# POWER_IN.net
KiCad netlist of a schematic drawn in Altium Designer
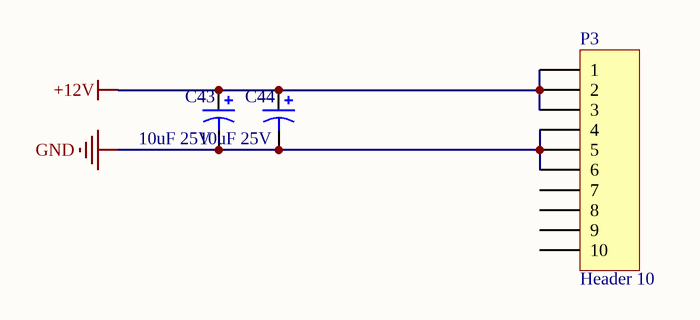
[diagram p0: POWER_IN.SchDoc]

(export (version "E")
  (design (tool "Eeschema 10.0.6"))
  (components
    (comp (ref "C43")
      (value "10uF 25V")
      (footprint "470UF_16V")
      (description "Polarized Capacitor (Radial)")
      (fields (field (name "Comment") "Cap Pol1") (field (name "PUBLISHER") "Altium Limited"))
      (libsource (lib "Miscellaneous Devices") (part "Cap Pol1"))
    )
    (comp (ref "C44")
      (value "10uF 25V")
      (footprint "470UF_16V")
      (description "Polarized Capacitor (Radial)")
      (fields (field (name "Comment") "Cap Pol1") (field (name "PUBLISHER") "Altium Limited"))
      (libsource (lib "Miscellaneous Devices") (part "Cap Pol1"))
    )
    (comp (ref "P3")
      (value "Header 10")
      (footprint "CON_MOL_5569_6P")
      (description "Header, 10-Pin")
      (fields (field (name "PUBLISHER") "Altium Limited"))
      (libsource (lib "Miscellaneous Connectors") (part "Header 10"))
    )
  )
  (nets
    (net (code "1") (name "+12V") (class "Default")
      (node (ref "C43") (pin "1") (pinfunction "1_1") (pintype "passive"))
      (node (ref "C44") (pin "1") (pinfunction "1_1") (pintype "passive"))
      (node (ref "P3") (pin "1") (pinfunction "1_1") (pintype "passive"))
      (node (ref "P3") (pin "2") (pinfunction "2_2") (pintype "passive"))
      (node (ref "P3") (pin "3") (pinfunction "3_3") (pintype "passive"))
    )
    (net (code "2") (name "GND") (class "Default")
      (node (ref "C43") (pin "2") (pinfunction "2_2") (pintype "passive"))
      (node (ref "C44") (pin "2") (pinfunction "2_2") (pintype "passive"))
      (node (ref "P3") (pin "4") (pinfunction "4_4") (pintype "passive"))
      (node (ref "P3") (pin "5") (pinfunction "5_5") (pintype "passive"))
      (node (ref "P3") (pin "6") (pinfunction "6_6") (pintype "passive"))
    )
    (net (code "3") (name "unconnected-(P3-Pad7)") (class "Default")
      (node (ref "P3") (pin "7") (pinfunction "7_7") (pintype "passive"))
    )
    (net (code "4") (name "unconnected-(P3-Pad8)") (class "Default")
      (node (ref "P3") (pin "8") (pinfunction "8_8") (pintype "passive"))
    )
    (net (code "5") (name "unconnected-(P3-Pad9)") (class "Default")
      (node (ref "P3") (pin "9") (pinfunction "9_9") (pintype "passive"))
    )
    (net (code "6") (name "unconnected-(P3-Pad10)") (class "Default")
      (node (ref "P3") (pin "10") (pinfunction "10_10") (pintype "passive"))
    )
  )
)
